# xyshield.net
KiCad netlist of a schematic drawn in EAGLE
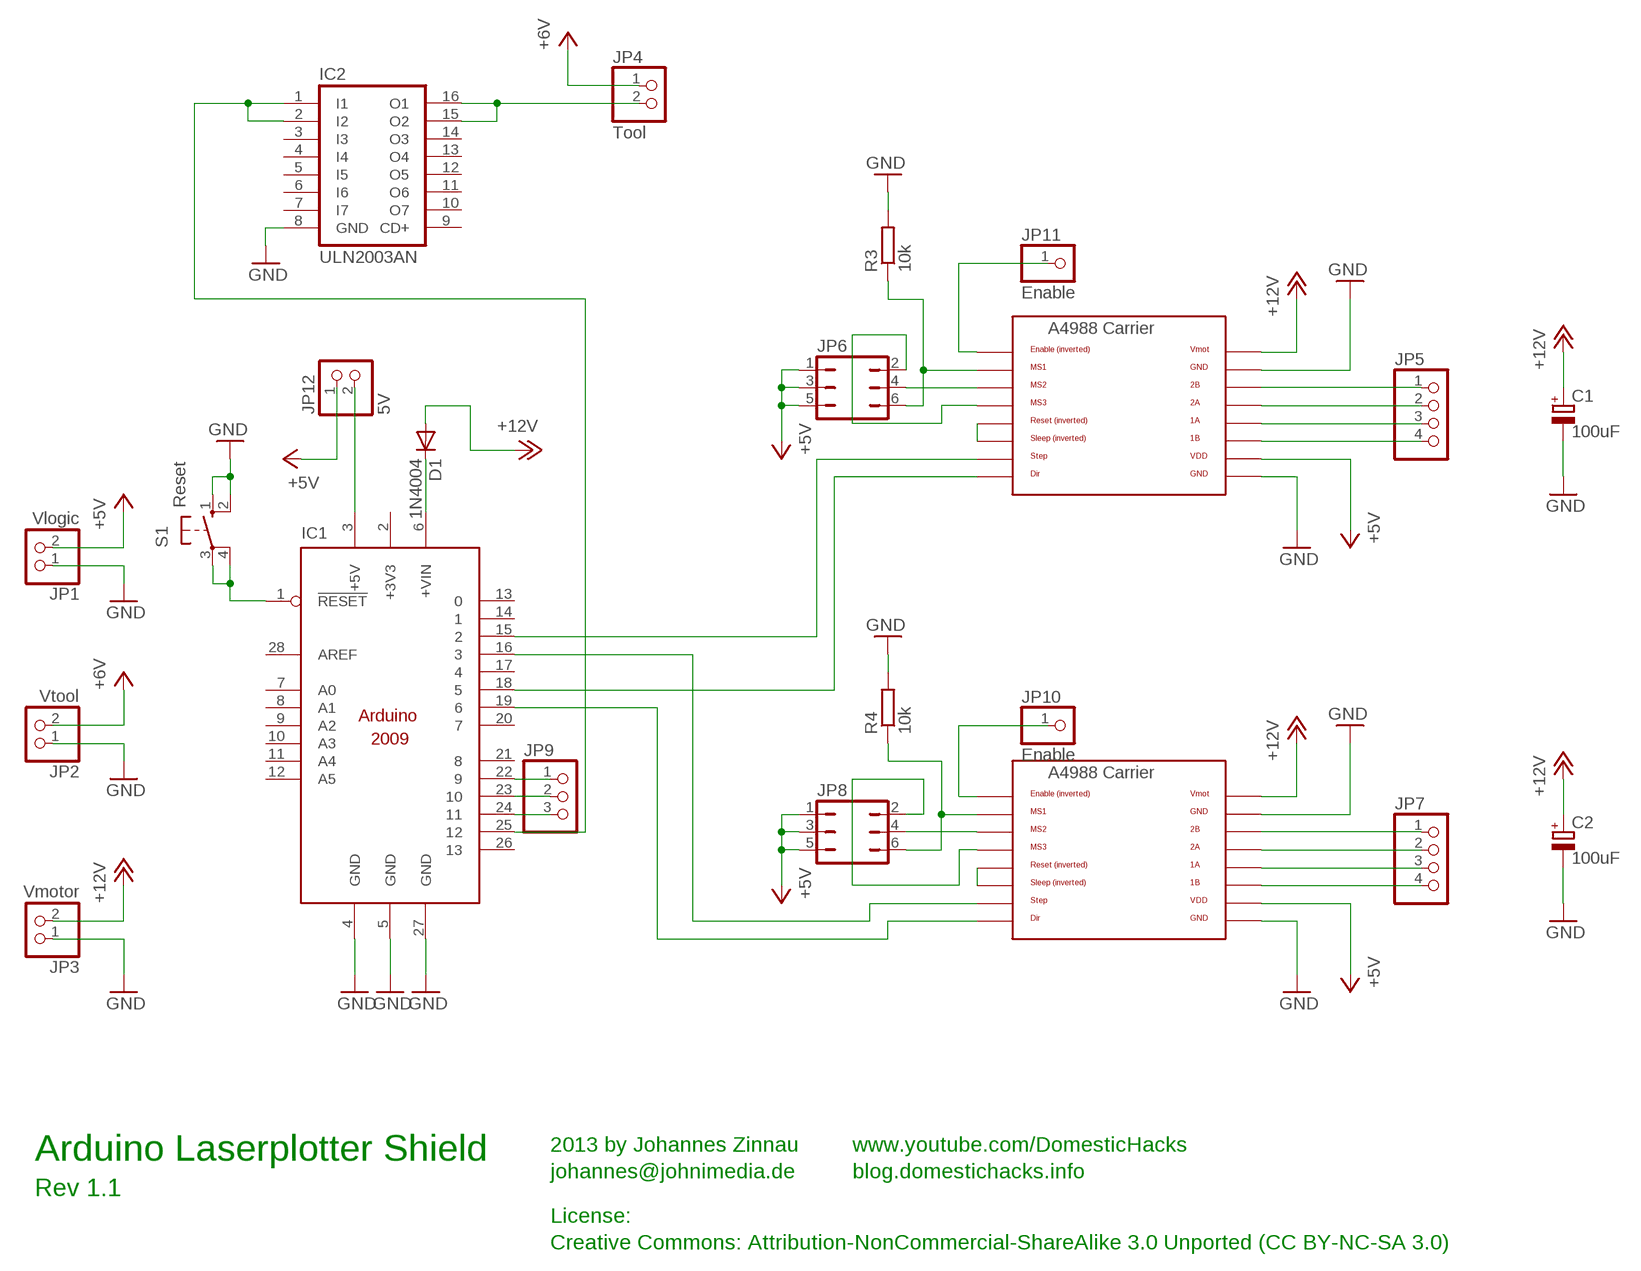
[diagram p0: schematic, sheet 1]

(export (version "E")
  (design (tool "Eeschema 10.0.6"))
  (components
    (comp (ref "C1")
      (value "100uF")
      (footprint "eagle-import:E2,5-6")
      (libsource (lib "eagle-import") (part "CPOL-EUE2.5-6"))
    )
    (comp (ref "C2")
      (value "100uF")
      (footprint "eagle-import:E2,5-6")
      (libsource (lib "eagle-import") (part "CPOL-EUE2.5-6"))
    )
    (comp (ref "D1")
      (value "1N4004")
      (footprint "eagle-import:DO41-10")
      (libsource (lib "eagle-import") (part "1N4004"))
    )
    (comp (ref "IC1")
      (value "Arduino")
      (footprint "eagle-import:ARDUINO2009")
      (libsource (lib "eagle-import") (part "ARDUINO2009_10"))
    )
    (comp (ref "IC2")
      (value "ULN2003AN")
      (footprint "eagle-import:DIL16")
      (libsource (lib "eagle-import") (part "ULN2003AN"))
    )
    (comp (ref "JP1")
      (value "Vlogic")
      (footprint "eagle-import:1X02")
      (libsource (lib "eagle-import") (part "PINHD-1X2"))
    )
    (comp (ref "JP2")
      (value "Vtool")
      (footprint "eagle-import:1X02")
      (libsource (lib "eagle-import") (part "PINHD-1X2"))
    )
    (comp (ref "JP3")
      (value "Vmotor")
      (footprint "eagle-import:1X02")
      (libsource (lib "eagle-import") (part "PINHD-1X2"))
    )
    (comp (ref "JP4")
      (value "Tool")
      (footprint "eagle-import:1X02")
      (libsource (lib "eagle-import") (part "PINHD-1X2"))
    )
    (comp (ref "JP5")
      (value "PINHD-1X4")
      (footprint "eagle-import:1X04")
      (libsource (lib "eagle-import") (part "PINHD-1X4"))
    )
    (comp (ref "JP6")
      (value "JP3Q")
      (footprint "eagle-import:JP3Q")
      (libsource (lib "eagle-import") (part "JP3Q"))
    )
    (comp (ref "JP7")
      (value "PINHD-1X4")
      (footprint "eagle-import:1X04")
      (libsource (lib "eagle-import") (part "PINHD-1X4"))
    )
    (comp (ref "JP8")
      (value "JP3Q")
      (footprint "eagle-import:JP3Q")
      (libsource (lib "eagle-import") (part "JP3Q"))
    )
    (comp (ref "JP9")
      (value "PINHD-1X3")
      (footprint "eagle-import:1X03")
      (libsource (lib "eagle-import") (part "PINHD-1X3"))
    )
    (comp (ref "JP10")
      (value "Enable")
      (footprint "eagle-import:1X01")
      (libsource (lib "eagle-import") (part "PINHD-1X1"))
    )
    (comp (ref "JP11")
      (value "Enable")
      (footprint "eagle-import:1X01")
      (libsource (lib "eagle-import") (part "PINHD-1X1"))
    )
    (comp (ref "JP12")
      (value "5V")
      (footprint "eagle-import:1X02")
      (libsource (lib "eagle-import") (part "PINHD-1X2"))
    )
    (comp (ref "R3")
      (value "10k")
      (footprint "eagle-import:0204V")
      (libsource (lib "eagle-import") (part "R-EU_0204/2V"))
    )
    (comp (ref "R4")
      (value "10k")
      (footprint "eagle-import:0204V")
      (libsource (lib "eagle-import") (part "R-EU_0204/2V"))
    )
    (comp (ref "S1")
      (value "Reset")
      (footprint "eagle-import:B3F-10XX")
      (fields (field (name "MPN") "B3F-1000"))
      (libsource (lib "eagle-import") (part "10-XX"))
    )
    (comp (ref "U$1")
      (value "POLOLU_A4983CARRIER")
      (footprint "eagle-import:A4988BREAKOUT")
      (libsource (lib "eagle-import") (part "POLOLU_A4983CARRIER"))
    )
    (comp (ref "U$2")
      (value "POLOLU_A4983CARRIER")
      (footprint "eagle-import:A4988BREAKOUT")
      (libsource (lib "eagle-import") (part "POLOLU_A4983CARRIER"))
    )
  )
  (nets
    (net (code "1") (name "+5V") (class "Default")
      (node (ref "JP1") (pin "2") (pinfunction "2_2") (pintype "passive"))
      (node (ref "JP12") (pin "1") (pinfunction "1_1") (pintype "passive"))
      (node (ref "JP6") (pin "1") (pinfunction "1_1") (pintype "passive"))
      (node (ref "JP6") (pin "3") (pinfunction "3_3") (pintype "passive"))
      (node (ref "JP6") (pin "5") (pinfunction "5_5") (pintype "passive"))
      (node (ref "JP8") (pin "1") (pinfunction "1_1") (pintype "passive"))
      (node (ref "JP8") (pin "3") (pinfunction "3_3") (pintype "passive"))
      (node (ref "JP8") (pin "5") (pinfunction "5_5") (pintype "passive"))
      (node (ref "U$1") (pin "VDD") (pinfunction "VDD_VDD") (pintype "power_in"))
      (node (ref "U$2") (pin "VDD") (pinfunction "VDD_VDD") (pintype "power_in"))
    )
    (net (code "2") (name "+6V") (class "Default")
      (node (ref "JP2") (pin "2") (pinfunction "2_2") (pintype "passive"))
      (node (ref "JP4") (pin "1") (pinfunction "1_1") (pintype "passive"))
    )
    (net (code "3") (name "+12V") (class "Default")
      (node (ref "C1") (pin "+") (pinfunction "+_+") (pintype "passive"))
      (node (ref "C2") (pin "+") (pinfunction "+_+") (pintype "passive"))
      (node (ref "D1") (pin "A") (pinfunction "A_A") (pintype "passive"))
      (node (ref "JP3") (pin "2") (pinfunction "2_2") (pintype "passive"))
      (node (ref "U$1") (pin "VMOT") (pinfunction "VMOT_VMOT") (pintype "power_in"))
      (node (ref "U$2") (pin "VMOT") (pinfunction "VMOT_VMOT") (pintype "power_in"))
    )
    (net (code "4") (name "/+3V3") (class "Default")
      (node (ref "IC1") (pin "2") (pinfunction "+3V3_2") (pintype "power_in"))
    )
    (net (code "5") (name "GND") (class "Default")
      (node (ref "C1") (pin "-") (pinfunction "-_-") (pintype "passive"))
      (node (ref "C2") (pin "-") (pinfunction "-_-") (pintype "passive"))
      (node (ref "IC1") (pin "27") (pinfunction "GND_27") (pintype "power_in"))
      (node (ref "IC1") (pin "4") (pinfunction "GND_4") (pintype "power_in"))
      (node (ref "IC1") (pin "5") (pinfunction "GND_5") (pintype "power_in"))
      (node (ref "IC2") (pin "8") (pinfunction "GND_8") (pintype "power_in"))
      (node (ref "JP1") (pin "1") (pinfunction "1_1") (pintype "passive"))
      (node (ref "JP2") (pin "1") (pinfunction "1_1") (pintype "passive"))
      (node (ref "JP3") (pin "1") (pinfunction "1_1") (pintype "passive"))
      (node (ref "R3") (pin "2") (pinfunction "2_2") (pintype "passive"))
      (node (ref "R4") (pin "2") (pinfunction "2_2") (pintype "passive"))
      (node (ref "S1") (pin "1") (pinfunction "S_1") (pintype "passive"))
      (node (ref "S1") (pin "2") (pinfunction "S1_2") (pintype "passive"))
      (node (ref "U$1") (pin "GND") (pinfunction "GND_GND") (pintype "power_in"))
      (node (ref "U$1") (pin "GND@0") (pinfunction "GND_GND@0") (pintype "power_in"))
      (node (ref "U$2") (pin "GND") (pinfunction "GND_GND") (pintype "power_in"))
      (node (ref "U$2") (pin "GND@0") (pinfunction "GND_GND@0") (pintype "power_in"))
    )
    (net (code "6") (name "Net-(IC1-+5V)") (class "Default")
      (node (ref "IC1") (pin "3") (pinfunction "+5V_3") (pintype "power_in"))
      (node (ref "JP12") (pin "2") (pinfunction "2_2") (pintype "passive"))
    )
    (net (code "7") (name "Net-(IC1-+VIN)") (class "Default")
      (node (ref "D1") (pin "C") (pinfunction "C_C") (pintype "passive"))
      (node (ref "IC1") (pin "6") (pinfunction "+VIN_6") (pintype "bidirectional"))
    )
    (net (code "8") (name "Net-(IC1-2)") (class "Default")
      (node (ref "IC1") (pin "15") (pinfunction "2_15") (pintype "bidirectional"))
      (node (ref "U$1") (pin "STEP") (pinfunction "STEP_STEP") (pintype "input"))
    )
    (net (code "9") (name "Net-(IC1-3)") (class "Default")
      (node (ref "IC1") (pin "16") (pinfunction "3_16") (pintype "bidirectional"))
      (node (ref "U$2") (pin "STEP") (pinfunction "STEP_STEP") (pintype "input"))
    )
    (net (code "10") (name "Net-(IC1-5)") (class "Default")
      (node (ref "IC1") (pin "18") (pinfunction "5_18") (pintype "bidirectional"))
      (node (ref "U$1") (pin "DIR") (pinfunction "DIR_DIR") (pintype "input"))
    )
    (net (code "11") (name "Net-(IC1-6)") (class "Default")
      (node (ref "IC1") (pin "19") (pinfunction "6_19") (pintype "bidirectional"))
      (node (ref "U$2") (pin "DIR") (pinfunction "DIR_DIR") (pintype "input"))
    )
    (net (code "12") (name "Net-(IC1-9)") (class "Default")
      (node (ref "IC1") (pin "22") (pinfunction "9_22") (pintype "bidirectional"))
      (node (ref "JP9") (pin "1") (pinfunction "1_1") (pintype "passive"))
    )
    (net (code "13") (name "Net-(IC1-10)") (class "Default")
      (node (ref "IC1") (pin "23") (pinfunction "10_23") (pintype "bidirectional"))
      (node (ref "JP9") (pin "2") (pinfunction "2_2") (pintype "passive"))
    )
    (net (code "14") (name "Net-(IC1-11)") (class "Default")
      (node (ref "IC1") (pin "24") (pinfunction "11_24") (pintype "bidirectional"))
      (node (ref "JP9") (pin "3") (pinfunction "3_3") (pintype "passive"))
    )
    (net (code "15") (name "Net-(IC1-12)") (class "Default")
      (node (ref "IC1") (pin "25") (pinfunction "12_25") (pintype "bidirectional"))
      (node (ref "IC2") (pin "1") (pinfunction "I1_1") (pintype "input"))
      (node (ref "IC2") (pin "2") (pinfunction "I2_2") (pintype "input"))
    )
    (net (code "16") (name "Net-(IC1-~{RESET})") (class "Default")
      (node (ref "IC1") (pin "1") (pinfunction "~{RESET}_1") (pintype "bidirectional"))
      (node (ref "S1") (pin "3") (pinfunction "P_3") (pintype "passive"))
      (node (ref "S1") (pin "4") (pinfunction "P1_4") (pintype "passive"))
    )
    (net (code "17") (name "Net-(IC2-O1)") (class "Default")
      (node (ref "IC2") (pin "15") (pinfunction "O2_15") (pintype "open_collector"))
      (node (ref "IC2") (pin "16") (pinfunction "O1_16") (pintype "open_collector"))
      (node (ref "JP4") (pin "2") (pinfunction "2_2") (pintype "passive"))
    )
    (net (code "18") (name "Net-(JP5-Pad1)") (class "Default")
      (node (ref "JP5") (pin "1") (pinfunction "1_1") (pintype "passive"))
      (node (ref "U$1") (pin "2B") (pinfunction "2B_2B") (pintype "output"))
    )
    (net (code "19") (name "Net-(JP5-Pad2)") (class "Default")
      (node (ref "JP5") (pin "2") (pinfunction "2_2") (pintype "passive"))
      (node (ref "U$1") (pin "2A") (pinfunction "2A_2A") (pintype "output"))
    )
    (net (code "20") (name "Net-(JP5-Pad3)") (class "Default")
      (node (ref "JP5") (pin "3") (pinfunction "3_3") (pintype "passive"))
      (node (ref "U$1") (pin "1A") (pinfunction "1A_1A") (pintype "output"))
    )
    (net (code "21") (name "Net-(JP5-Pad4)") (class "Default")
      (node (ref "JP5") (pin "4") (pinfunction "4_4") (pintype "passive"))
      (node (ref "U$1") (pin "1B") (pinfunction "1B_1B") (pintype "output"))
    )
    (net (code "22") (name "Net-(JP6-Pad2)") (class "Default")
      (node (ref "JP6") (pin "2") (pinfunction "2_2") (pintype "passive"))
      (node (ref "U$1") (pin "MS3") (pinfunction "MS3_MS3") (pintype "input"))
    )
    (net (code "23") (name "Net-(JP6-Pad4)") (class "Default")
      (node (ref "JP6") (pin "4") (pinfunction "4_4") (pintype "passive"))
      (node (ref "U$1") (pin "MS2") (pinfunction "MS2_MS2") (pintype "input"))
    )
    (net (code "24") (name "Net-(JP6-Pad6)") (class "Default")
      (node (ref "JP6") (pin "6") (pinfunction "6_6") (pintype "passive"))
      (node (ref "R3") (pin "1") (pinfunction "1_1") (pintype "passive"))
      (node (ref "U$1") (pin "MS1") (pinfunction "MS1_MS1") (pintype "input"))
    )
    (net (code "25") (name "Net-(JP7-Pad1)") (class "Default")
      (node (ref "JP7") (pin "1") (pinfunction "1_1") (pintype "passive"))
      (node (ref "U$2") (pin "2B") (pinfunction "2B_2B") (pintype "output"))
    )
    (net (code "26") (name "Net-(JP7-Pad2)") (class "Default")
      (node (ref "JP7") (pin "2") (pinfunction "2_2") (pintype "passive"))
      (node (ref "U$2") (pin "2A") (pinfunction "2A_2A") (pintype "output"))
    )
    (net (code "27") (name "Net-(JP7-Pad3)") (class "Default")
      (node (ref "JP7") (pin "3") (pinfunction "3_3") (pintype "passive"))
      (node (ref "U$2") (pin "1A") (pinfunction "1A_1A") (pintype "output"))
    )
    (net (code "28") (name "Net-(JP7-Pad4)") (class "Default")
      (node (ref "JP7") (pin "4") (pinfunction "4_4") (pintype "passive"))
      (node (ref "U$2") (pin "1B") (pinfunction "1B_1B") (pintype "output"))
    )
    (net (code "29") (name "Net-(JP8-Pad2)") (class "Default")
      (node (ref "JP8") (pin "2") (pinfunction "2_2") (pintype "passive"))
      (node (ref "U$2") (pin "MS3") (pinfunction "MS3_MS3") (pintype "input"))
    )
    (net (code "30") (name "Net-(JP8-Pad4)") (class "Default")
      (node (ref "JP8") (pin "4") (pinfunction "4_4") (pintype "passive"))
      (node (ref "U$2") (pin "MS2") (pinfunction "MS2_MS2") (pintype "input"))
    )
    (net (code "31") (name "Net-(JP8-Pad6)") (class "Default")
      (node (ref "JP8") (pin "6") (pinfunction "6_6") (pintype "passive"))
      (node (ref "R4") (pin "1") (pinfunction "1_1") (pintype "passive"))
      (node (ref "U$2") (pin "MS1") (pinfunction "MS1_MS1") (pintype "input"))
    )
    (net (code "32") (name "Net-(JP10-Pad1)") (class "Default")
      (node (ref "JP10") (pin "1") (pinfunction "1_1") (pintype "passive"))
      (node (ref "U$2") (pin "EN") (pinfunction "EN_EN") (pintype "input"))
    )
    (net (code "33") (name "Net-(JP11-Pad1)") (class "Default")
      (node (ref "JP11") (pin "1") (pinfunction "1_1") (pintype "passive"))
      (node (ref "U$1") (pin "EN") (pinfunction "EN_EN") (pintype "input"))
    )
    (net (code "34") (name "Net-(U$1-SLEEP)") (class "Default")
      (node (ref "U$1") (pin "RST") (pinfunction "RST_RST") (pintype "input"))
      (node (ref "U$1") (pin "SLP") (pinfunction "SLEEP_SLP") (pintype "input"))
    )
    (net (code "35") (name "Net-(U$2-SLEEP)") (class "Default")
      (node (ref "U$2") (pin "RST") (pinfunction "RST_RST") (pintype "input"))
      (node (ref "U$2") (pin "SLP") (pinfunction "SLEEP_SLP") (pintype "input"))
    )
    (net (code "36") (name "unconnected-(IC1-0-Pad13)") (class "Default")
      (node (ref "IC1") (pin "13") (pinfunction "0_13") (pintype "bidirectional"))
    )
    (net (code "37") (name "unconnected-(IC1-1-Pad14)") (class "Default")
      (node (ref "IC1") (pin "14") (pinfunction "1_14") (pintype "bidirectional"))
    )
    (net (code "38") (name "unconnected-(IC1-4-Pad17)") (class "Default")
      (node (ref "IC1") (pin "17") (pinfunction "4_17") (pintype "bidirectional"))
    )
    (net (code "39") (name "unconnected-(IC1-7-Pad20)") (class "Default")
      (node (ref "IC1") (pin "20") (pinfunction "7_20") (pintype "bidirectional"))
    )
    (net (code "40") (name "unconnected-(IC1-8-Pad21)") (class "Default")
      (node (ref "IC1") (pin "21") (pinfunction "8_21") (pintype "bidirectional"))
    )
    (net (code "41") (name "unconnected-(IC1-13-Pad26)") (class "Default")
      (node (ref "IC1") (pin "26") (pinfunction "13_26") (pintype "bidirectional"))
    )
    (net (code "42") (name "unconnected-(IC1-A0-Pad7)") (class "Default")
      (node (ref "IC1") (pin "7") (pinfunction "A0_7") (pintype "bidirectional"))
    )
    (net (code "43") (name "unconnected-(IC1-A1-Pad8)") (class "Default")
      (node (ref "IC1") (pin "8") (pinfunction "A1_8") (pintype "bidirectional"))
    )
    (net (code "44") (name "unconnected-(IC1-A2-Pad9)") (class "Default")
      (node (ref "IC1") (pin "9") (pinfunction "A2_9") (pintype "bidirectional"))
    )
    (net (code "45") (name "unconnected-(IC1-A3-Pad10)") (class "Default")
      (node (ref "IC1") (pin "10") (pinfunction "A3_10") (pintype "bidirectional"))
    )
    (net (code "46") (name "unconnected-(IC1-A4-Pad11)") (class "Default")
      (node (ref "IC1") (pin "11") (pinfunction "A4_11") (pintype "bidirectional"))
    )
    (net (code "47") (name "unconnected-(IC1-A5-Pad12)") (class "Default")
      (node (ref "IC1") (pin "12") (pinfunction "A5_12") (pintype "bidirectional"))
    )
    (net (code "48") (name "unconnected-(IC1-AREF-Pad28)") (class "Default")
      (node (ref "IC1") (pin "28") (pinfunction "AREF_28") (pintype "bidirectional"))
    )
    (net (code "49") (name "unconnected-(IC2-CD+-Pad9)") (class "Default")
      (node (ref "IC2") (pin "9") (pinfunction "CD+_9") (pintype "passive"))
    )
    (net (code "50") (name "unconnected-(IC2-I3-Pad3)") (class "Default")
      (node (ref "IC2") (pin "3") (pinfunction "I3_3") (pintype "input"))
    )
    (net (code "51") (name "unconnected-(IC2-I4-Pad4)") (class "Default")
      (node (ref "IC2") (pin "4") (pinfunction "I4_4") (pintype "input"))
    )
    (net (code "52") (name "unconnected-(IC2-I5-Pad5)") (class "Default")
      (node (ref "IC2") (pin "5") (pinfunction "I5_5") (pintype "input"))
    )
    (net (code "53") (name "unconnected-(IC2-I6-Pad6)") (class "Default")
      (node (ref "IC2") (pin "6") (pinfunction "I6_6") (pintype "input"))
    )
    (net (code "54") (name "unconnected-(IC2-I7-Pad7)") (class "Default")
      (node (ref "IC2") (pin "7") (pinfunction "I7_7") (pintype "input"))
    )
    (net (code "55") (name "unconnected-(IC2-O3-Pad14)") (class "Default")
      (node (ref "IC2") (pin "14") (pinfunction "O3_14") (pintype "open_collector"))
    )
    (net (code "56") (name "unconnected-(IC2-O4-Pad13)") (class "Default")
      (node (ref "IC2") (pin "13") (pinfunction "O4_13") (pintype "open_collector"))
    )
    (net (code "57") (name "unconnected-(IC2-O5-Pad12)") (class "Default")
      (node (ref "IC2") (pin "12") (pinfunction "O5_12") (pintype "open_collector"))
    )
    (net (code "58") (name "unconnected-(IC2-O6-Pad11)") (class "Default")
      (node (ref "IC2") (pin "11") (pinfunction "O6_11") (pintype "open_collector"))
    )
    (net (code "59") (name "unconnected-(IC2-O7-Pad10)") (class "Default")
      (node (ref "IC2") (pin "10") (pinfunction "O7_10") (pintype "open_collector"))
    )
  )
)
